# main.net
KiCad netlist of a schematic drawn in EAGLE
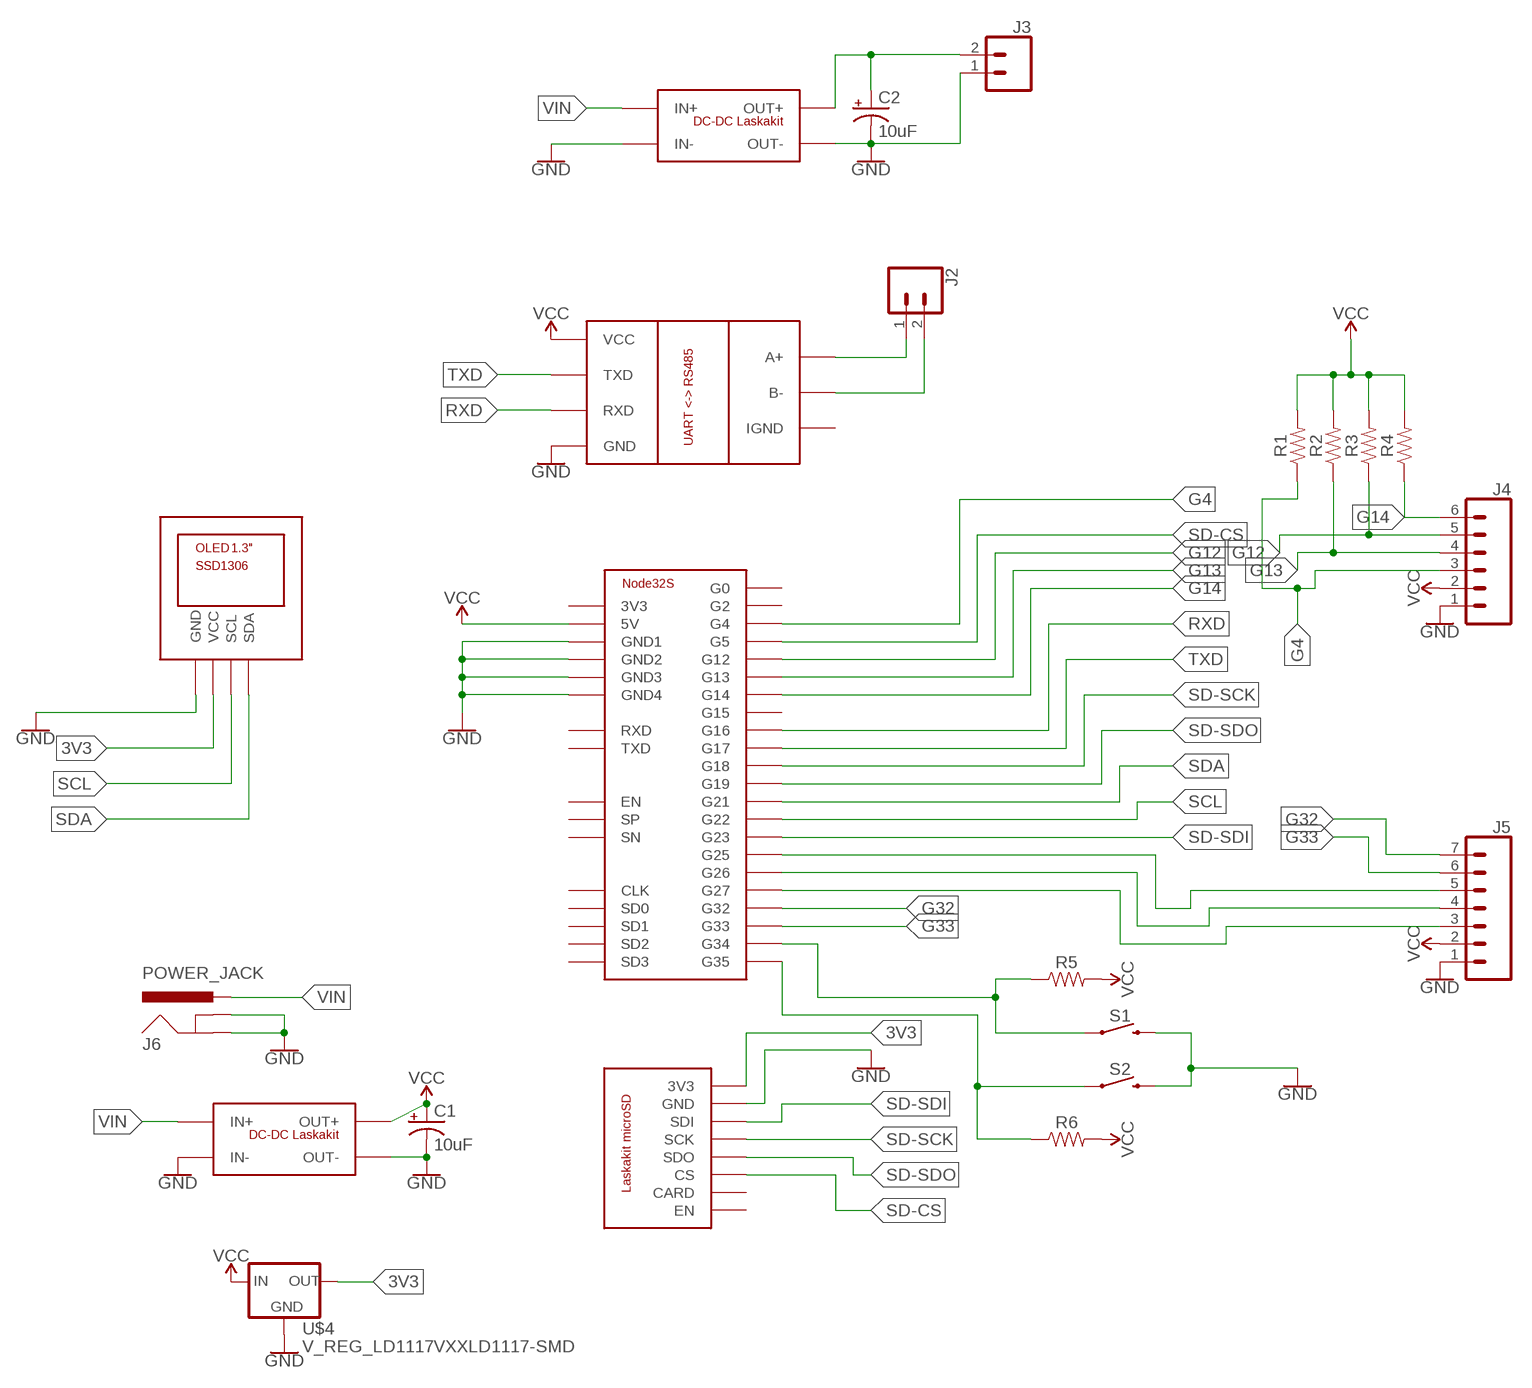
[diagram p0: schematic, sheet 1]

(export (version "E")
  (design (tool "Eeschema 10.0.6"))
  (components
    (comp (ref "C1")
      (value "10uF")
      (footprint "eagle-import:CPOL-RADIAL-2.5MM-5MM")
      (libsource (lib "eagle-import") (part "10UF-POLAR-RADIAL-2.5MM-25V-20%"))
    )
    (comp (ref "C2")
      (value "10uF")
      (footprint "eagle-import:CPOL-RADIAL-2.5MM-5MM")
      (libsource (lib "eagle-import") (part "10UF-POLAR-RADIAL-2.5MM-25V-20%"))
    )
    (comp (ref "J2")
      (value "CONN_025MM")
      (footprint "eagle-import:SCREWTERMINAL-5MM-2")
      (libsource (lib "eagle-import") (part "CONN_025MM"))
    )
    (comp (ref "J3")
      (value "CONN_025MM")
      (footprint "eagle-import:SCREWTERMINAL-5MM-2")
      (libsource (lib "eagle-import") (part "CONN_025MM"))
    )
    (comp (ref "J4")
      (value "CONN_06NO_SILK_FEMALE_PTH")
      (footprint "eagle-import:1X06_NO_SILK")
      (libsource (lib "eagle-import") (part "CONN_06NO_SILK_FEMALE_PTH"))
    )
    (comp (ref "J5")
      (value "CONN_07NO_SILK")
      (footprint "eagle-import:1X07_NO_SILK")
      (libsource (lib "eagle-import") (part "CONN_07NO_SILK"))
    )
    (comp (ref "J6")
      (value "POWER_JACK")
      (footprint "eagle-import:POWER_JACK_PTH")
      (libsource (lib "eagle-import") (part "POWER_JACK"))
    )
    (comp (ref "R1")
      (value "RESISTOR0805")
      (footprint "eagle-import:0805")
      (libsource (lib "eagle-import") (part "RESISTOR0805"))
    )
    (comp (ref "R2")
      (value "RESISTOR0805")
      (footprint "eagle-import:0805")
      (libsource (lib "eagle-import") (part "RESISTOR0805"))
    )
    (comp (ref "R3")
      (value "RESISTOR0805")
      (footprint "eagle-import:0805")
      (libsource (lib "eagle-import") (part "RESISTOR0805"))
    )
    (comp (ref "R4")
      (value "RESISTOR0805")
      (footprint "eagle-import:0805")
      (libsource (lib "eagle-import") (part "RESISTOR0805"))
    )
    (comp (ref "R5")
      (value "RESISTOR0805")
      (footprint "eagle-import:0805")
      (libsource (lib "eagle-import") (part "RESISTOR0805"))
    )
    (comp (ref "R6")
      (value "RESISTOR0805")
      (footprint "eagle-import:0805")
      (libsource (lib "eagle-import") (part "RESISTOR0805"))
    )
    (comp (ref "S1")
      (value "MOMENTARY-SWITCH-SPST-PTH-12MM")
      (footprint "eagle-import:TACTILE_SWITCH_PTH_12MM")
      (libsource (lib "eagle-import") (part "MOMENTARY-SWITCH-SPST-PTH-12MM"))
    )
    (comp (ref "S2")
      (value "MOMENTARY-SWITCH-SPST-PTH-12MM")
      (footprint "eagle-import:TACTILE_SWITCH_PTH_12MM")
      (libsource (lib "eagle-import") (part "MOMENTARY-SWITCH-SPST-PTH-12MM"))
    )
    (comp (ref "U$1")
      (value "NODE32S")
      (footprint "eagle-import:NODE32S")
      (libsource (lib "eagle-import") (part "NODE32S"))
    )
    (comp (ref "U$2")
      (value "LASKAKIT_SDCARD")
      (footprint "eagle-import:LASKAKIT_SD_MODULE")
      (libsource (lib "eagle-import") (part "LASKAKIT_SDCARD"))
    )
    (comp (ref "U$3")
      (value "DC-DC-LASKAKIT")
      (footprint "eagle-import:DC-DC-MODULE-LASKAKIT")
      (libsource (lib "eagle-import") (part "DC-DC-LASKAKIT"))
    )
    (comp (ref "U$4")
      (value "V_REG_LD1117VXXLD1117-SMD")
      (footprint "eagle-import:SOT223")
      (libsource (lib "eagle-import") (part "V_REG_LD1117VXXLD1117-SMD"))
    )
    (comp (ref "U$5")
      (value "RS485-UART-CONVERTER")
      (footprint "eagle-import:RS485_MODULE")
      (libsource (lib "eagle-import") (part "RS485-UART-CONVERTER"))
    )
    (comp (ref "U$6")
      (value "OLED_0.96_I2C")
      (footprint "eagle-import:OLED_0.96")
      (libsource (lib "eagle-import") (part "OLED_0.96_I2C"))
    )
    (comp (ref "U$7")
      (value "DC-DC-LASKAKIT")
      (footprint "eagle-import:DC-DC-MODULE-LASKAKIT")
      (libsource (lib "eagle-import") (part "DC-DC-LASKAKIT"))
    )
  )
  (nets
    (net (code "1") (name "3V3") (class "Default")
      (node (ref "U$2") (pin "P$1") (pinfunction "3V3_P$1") (pintype "bidirectional"))
      (node (ref "U$4") (pin "2") (pinfunction "OUT_2") (pintype "passive"))
      (node (ref "U$6") (pin "P$2") (pinfunction "VCC_P$2") (pintype "bidirectional"))
    )
    (net (code "2") (name "G4") (class "Default")
      (node (ref "J4") (pin "3") (pinfunction "3_3") (pintype "passive"))
      (node (ref "R1") (pin "1") (pinfunction "1_1") (pintype "passive"))
      (node (ref "U$1") (pin "P$26") (pinfunction "G4_P$26") (pintype "bidirectional"))
    )
    (net (code "3") (name "G12") (class "Default")
      (node (ref "J4") (pin "5") (pinfunction "5_5") (pintype "passive"))
      (node (ref "R3") (pin "1") (pinfunction "1_1") (pintype "passive"))
      (node (ref "U$1") (pin "P$13") (pinfunction "G12_P$13") (pintype "bidirectional"))
    )
    (net (code "4") (name "G13") (class "Default")
      (node (ref "J4") (pin "4") (pinfunction "4_4") (pintype "passive"))
      (node (ref "R2") (pin "1") (pinfunction "1_1") (pintype "passive"))
      (node (ref "U$1") (pin "P$15") (pinfunction "G13_P$15") (pintype "bidirectional"))
    )
    (net (code "5") (name "G14") (class "Default")
      (node (ref "J4") (pin "6") (pinfunction "6_6") (pintype "passive"))
      (node (ref "R4") (pin "1") (pinfunction "1_1") (pintype "passive"))
      (node (ref "U$1") (pin "P$12") (pinfunction "G14_P$12") (pintype "bidirectional"))
    )
    (net (code "6") (name "G32") (class "Default")
      (node (ref "J5") (pin "7") (pinfunction "7_7") (pintype "passive"))
      (node (ref "U$1") (pin "P$7") (pinfunction "G32_P$7") (pintype "bidirectional"))
    )
    (net (code "7") (name "G33") (class "Default")
      (node (ref "J5") (pin "6") (pinfunction "6_6") (pintype "passive"))
      (node (ref "U$1") (pin "P$8") (pinfunction "G33_P$8") (pintype "bidirectional"))
    )
    (net (code "8") (name "GND") (class "Default")
      (node (ref "C1") (pin "2") (pinfunction "-_2") (pintype "passive"))
      (node (ref "C2") (pin "2") (pinfunction "-_2") (pintype "passive"))
      (node (ref "J3") (pin "1") (pinfunction "1_1") (pintype "passive"))
      (node (ref "J4") (pin "1") (pinfunction "1_1") (pintype "passive"))
      (node (ref "J5") (pin "1") (pinfunction "1_1") (pintype "passive"))
      (node (ref "J6") (pin "GND") (pinfunction "GND_GND") (pintype "bidirectional"))
      (node (ref "J6") (pin "GNDBREAK") (pinfunction "GNDBREAK_GNDBREAK") (pintype "bidirectional"))
      (node (ref "S1") (pin "3") (pinfunction "2_3") (pintype "passive"))
      (node (ref "S2") (pin "3") (pinfunction "2_3") (pintype "passive"))
      (node (ref "U$1") (pin "P$14") (pinfunction "GND1_P$14") (pintype "bidirectional"))
      (node (ref "U$1") (pin "P$18") (pinfunction "GND2_P$18") (pintype "bidirectional"))
      (node (ref "U$1") (pin "P$32") (pinfunction "GND3_P$32") (pintype "bidirectional"))
      (node (ref "U$1") (pin "P$38") (pinfunction "GND4_P$38") (pintype "bidirectional"))
      (node (ref "U$2") (pin "P$2") (pinfunction "GND_P$2") (pintype "bidirectional"))
      (node (ref "U$3") (pin "IN-") (pinfunction "IN-_IN-") (pintype "bidirectional"))
      (node (ref "U$3") (pin "OUT-") (pinfunction "OUT-_OUT-") (pintype "bidirectional"))
      (node (ref "U$4") (pin "1") (pinfunction "GND_1") (pintype "input"))
      (node (ref "U$5") (pin "GND") (pinfunction "GND_GND") (pintype "bidirectional"))
      (node (ref "U$6") (pin "P$1") (pinfunction "GND_P$1") (pintype "bidirectional"))
      (node (ref "U$7") (pin "IN-") (pinfunction "IN-_IN-") (pintype "bidirectional"))
      (node (ref "U$7") (pin "OUT-") (pinfunction "OUT-_OUT-") (pintype "bidirectional"))
    )
    (net (code "9") (name "Net-(C2-+)") (class "Default")
      (node (ref "C2") (pin "1") (pinfunction "+_1") (pintype "passive"))
      (node (ref "J3") (pin "2") (pinfunction "2_2") (pintype "passive"))
      (node (ref "U$7") (pin "OUT+") (pinfunction "OUT+_OUT+") (pintype "bidirectional"))
    )
    (net (code "10") (name "Net-(J2-Pad1)") (class "Default")
      (node (ref "J2") (pin "1") (pinfunction "1_1") (pintype "passive"))
      (node (ref "U$5") (pin "A+") (pinfunction "A+_A+") (pintype "bidirectional"))
    )
    (net (code "11") (name "Net-(J2-Pad2)") (class "Default")
      (node (ref "J2") (pin "2") (pinfunction "2_2") (pintype "passive"))
      (node (ref "U$5") (pin "B-") (pinfunction "B-_B-") (pintype "bidirectional"))
    )
    (net (code "12") (name "Net-(U$1-G25)") (class "Default")
      (node (ref "J5") (pin "5") (pinfunction "5_5") (pintype "passive"))
      (node (ref "U$1") (pin "P$9") (pinfunction "G25_P$9") (pintype "bidirectional"))
    )
    (net (code "13") (name "Net-(U$1-G26)") (class "Default")
      (node (ref "J5") (pin "4") (pinfunction "4_4") (pintype "passive"))
      (node (ref "U$1") (pin "P$10") (pinfunction "G26_P$10") (pintype "bidirectional"))
    )
    (net (code "14") (name "Net-(U$1-G27)") (class "Default")
      (node (ref "J5") (pin "3") (pinfunction "3_3") (pintype "passive"))
      (node (ref "U$1") (pin "P$11") (pinfunction "G27_P$11") (pintype "bidirectional"))
    )
    (net (code "15") (name "Net-(U$1-G34)") (class "Default")
      (node (ref "R5") (pin "1") (pinfunction "1_1") (pintype "passive"))
      (node (ref "S1") (pin "1") (pinfunction "1_1") (pintype "passive"))
      (node (ref "U$1") (pin "P$5") (pinfunction "G34_P$5") (pintype "bidirectional"))
    )
    (net (code "16") (name "Net-(U$1-G35)") (class "Default")
      (node (ref "R6") (pin "1") (pinfunction "1_1") (pintype "passive"))
      (node (ref "S2") (pin "1") (pinfunction "1_1") (pintype "passive"))
      (node (ref "U$1") (pin "P$6") (pinfunction "G35_P$6") (pintype "bidirectional"))
    )
    (net (code "17") (name "RXD") (class "Default")
      (node (ref "U$1") (pin "P$27") (pinfunction "G16_P$27") (pintype "bidirectional"))
      (node (ref "U$5") (pin "RXD") (pinfunction "RXD_RXD") (pintype "bidirectional"))
    )
    (net (code "18") (name "SCL") (class "Default")
      (node (ref "U$1") (pin "P$36") (pinfunction "G22_P$36") (pintype "bidirectional"))
      (node (ref "U$6") (pin "P$3") (pinfunction "SCL_P$3") (pintype "bidirectional"))
    )
    (net (code "19") (name "SD-CS") (class "Default")
      (node (ref "U$1") (pin "P$29") (pinfunction "G5_P$29") (pintype "bidirectional"))
      (node (ref "U$2") (pin "P$6") (pinfunction "CS_P$6") (pintype "bidirectional"))
    )
    (net (code "20") (name "SD-SCK") (class "Default")
      (node (ref "U$1") (pin "P$30") (pinfunction "G18_P$30") (pintype "bidirectional"))
      (node (ref "U$2") (pin "P$4") (pinfunction "SCK_P$4") (pintype "bidirectional"))
    )
    (net (code "21") (name "SD-SDI") (class "Default")
      (node (ref "U$1") (pin "P$37") (pinfunction "G23_P$37") (pintype "bidirectional"))
      (node (ref "U$2") (pin "P$3") (pinfunction "SDI_P$3") (pintype "bidirectional"))
    )
    (net (code "22") (name "SD-SDO") (class "Default")
      (node (ref "U$1") (pin "P$31") (pinfunction "G19_P$31") (pintype "bidirectional"))
      (node (ref "U$2") (pin "P$5") (pinfunction "SDO_P$5") (pintype "bidirectional"))
    )
    (net (code "23") (name "SDA") (class "Default")
      (node (ref "U$1") (pin "P$33") (pinfunction "G21_P$33") (pintype "bidirectional"))
      (node (ref "U$6") (pin "P$4") (pinfunction "SDA_P$4") (pintype "bidirectional"))
    )
    (net (code "24") (name "TXD") (class "Default")
      (node (ref "U$1") (pin "P$28") (pinfunction "G17_P$28") (pintype "bidirectional"))
      (node (ref "U$5") (pin "TXD") (pinfunction "TXD_TXD") (pintype "bidirectional"))
    )
    (net (code "25") (name "VCC") (class "Default")
      (node (ref "C1") (pin "1") (pinfunction "+_1") (pintype "passive"))
      (node (ref "J4") (pin "2") (pinfunction "2_2") (pintype "passive"))
      (node (ref "J5") (pin "2") (pinfunction "2_2") (pintype "passive"))
      (node (ref "R1") (pin "2") (pinfunction "2_2") (pintype "passive"))
      (node (ref "R2") (pin "2") (pinfunction "2_2") (pintype "passive"))
      (node (ref "R3") (pin "2") (pinfunction "2_2") (pintype "passive"))
      (node (ref "R4") (pin "2") (pinfunction "2_2") (pintype "passive"))
      (node (ref "R5") (pin "2") (pinfunction "2_2") (pintype "passive"))
      (node (ref "R6") (pin "2") (pinfunction "2_2") (pintype "passive"))
      (node (ref "U$1") (pin "P$19") (pinfunction "5V_P$19") (pintype "bidirectional"))
      (node (ref "U$3") (pin "OUT+") (pinfunction "OUT+_OUT+") (pintype "bidirectional"))
      (node (ref "U$4") (pin "3") (pinfunction "IN_3") (pintype "input"))
      (node (ref "U$5") (pin "VCC") (pinfunction "VCC_VCC") (pintype "bidirectional"))
    )
    (net (code "26") (name "VIN") (class "Default")
      (node (ref "J6") (pin "PWR") (pinfunction "PWR_PWR") (pintype "bidirectional"))
      (node (ref "U$3") (pin "IN+") (pinfunction "IN+_IN+") (pintype "bidirectional"))
      (node (ref "U$7") (pin "IN+") (pinfunction "IN+_IN+") (pintype "bidirectional"))
    )
    (net (code "27") (name "unconnected-(U$1-3V3-PadP$1)") (class "Default")
      (node (ref "U$1") (pin "P$1") (pinfunction "3V3_P$1") (pintype "bidirectional"))
    )
    (net (code "28") (name "unconnected-(U$1-CLK-PadP$20)") (class "Default")
      (node (ref "U$1") (pin "P$20") (pinfunction "CLK_P$20") (pintype "bidirectional"))
    )
    (net (code "29") (name "unconnected-(U$1-EN-PadP$2)") (class "Default")
      (node (ref "U$1") (pin "P$2") (pinfunction "EN_P$2") (pintype "bidirectional"))
    )
    (net (code "30") (name "unconnected-(U$1-G0-PadP$25)") (class "Default")
      (node (ref "U$1") (pin "P$25") (pinfunction "G0_P$25") (pintype "bidirectional"))
    )
    (net (code "31") (name "unconnected-(U$1-G2-PadP$24)") (class "Default")
      (node (ref "U$1") (pin "P$24") (pinfunction "G2_P$24") (pintype "bidirectional"))
    )
    (net (code "32") (name "unconnected-(U$1-G15-PadP$23)") (class "Default")
      (node (ref "U$1") (pin "P$23") (pinfunction "G15_P$23") (pintype "bidirectional"))
    )
    (net (code "33") (name "unconnected-(U$1-RXD-PadP$34)") (class "Default")
      (node (ref "U$1") (pin "P$34") (pinfunction "RXD_P$34") (pintype "bidirectional"))
    )
    (net (code "34") (name "unconnected-(U$1-SD0-PadP$21)") (class "Default")
      (node (ref "U$1") (pin "P$21") (pinfunction "SD0_P$21") (pintype "bidirectional"))
    )
    (net (code "35") (name "unconnected-(U$1-SD1-PadP$22)") (class "Default")
      (node (ref "U$1") (pin "P$22") (pinfunction "SD1_P$22") (pintype "bidirectional"))
    )
    (net (code "36") (name "unconnected-(U$1-SD2-PadP$16)") (class "Default")
      (node (ref "U$1") (pin "P$16") (pinfunction "SD2_P$16") (pintype "bidirectional"))
    )
    (net (code "37") (name "unconnected-(U$1-SD3-PadP$17)") (class "Default")
      (node (ref "U$1") (pin "P$17") (pinfunction "SD3_P$17") (pintype "bidirectional"))
    )
    (net (code "38") (name "unconnected-(U$1-SN-PadP$4)") (class "Default")
      (node (ref "U$1") (pin "P$4") (pinfunction "SN_P$4") (pintype "bidirectional"))
    )
    (net (code "39") (name "unconnected-(U$1-SP-PadP$3)") (class "Default")
      (node (ref "U$1") (pin "P$3") (pinfunction "SP_P$3") (pintype "bidirectional"))
    )
    (net (code "40") (name "unconnected-(U$1-TXD-PadP$35)") (class "Default")
      (node (ref "U$1") (pin "P$35") (pinfunction "TXD_P$35") (pintype "bidirectional"))
    )
    (net (code "41") (name "unconnected-(U$2-CARD-PadP$7)") (class "Default")
      (node (ref "U$2") (pin "P$7") (pinfunction "CARD_P$7") (pintype "bidirectional"))
    )
    (net (code "42") (name "unconnected-(U$2-EN-PadP$8)") (class "Default")
      (node (ref "U$2") (pin "P$8") (pinfunction "EN_P$8") (pintype "bidirectional"))
    )
    (net (code "43") (name "unconnected-(U$5-IGND-PadISOGND)") (class "Default")
      (node (ref "U$5") (pin "ISOGND") (pinfunction "IGND_ISOGND") (pintype "bidirectional"))
    )
  )
)
